# bolid-inputs-lv.net
KiCad netlist of a schematic drawn in Altium Designer
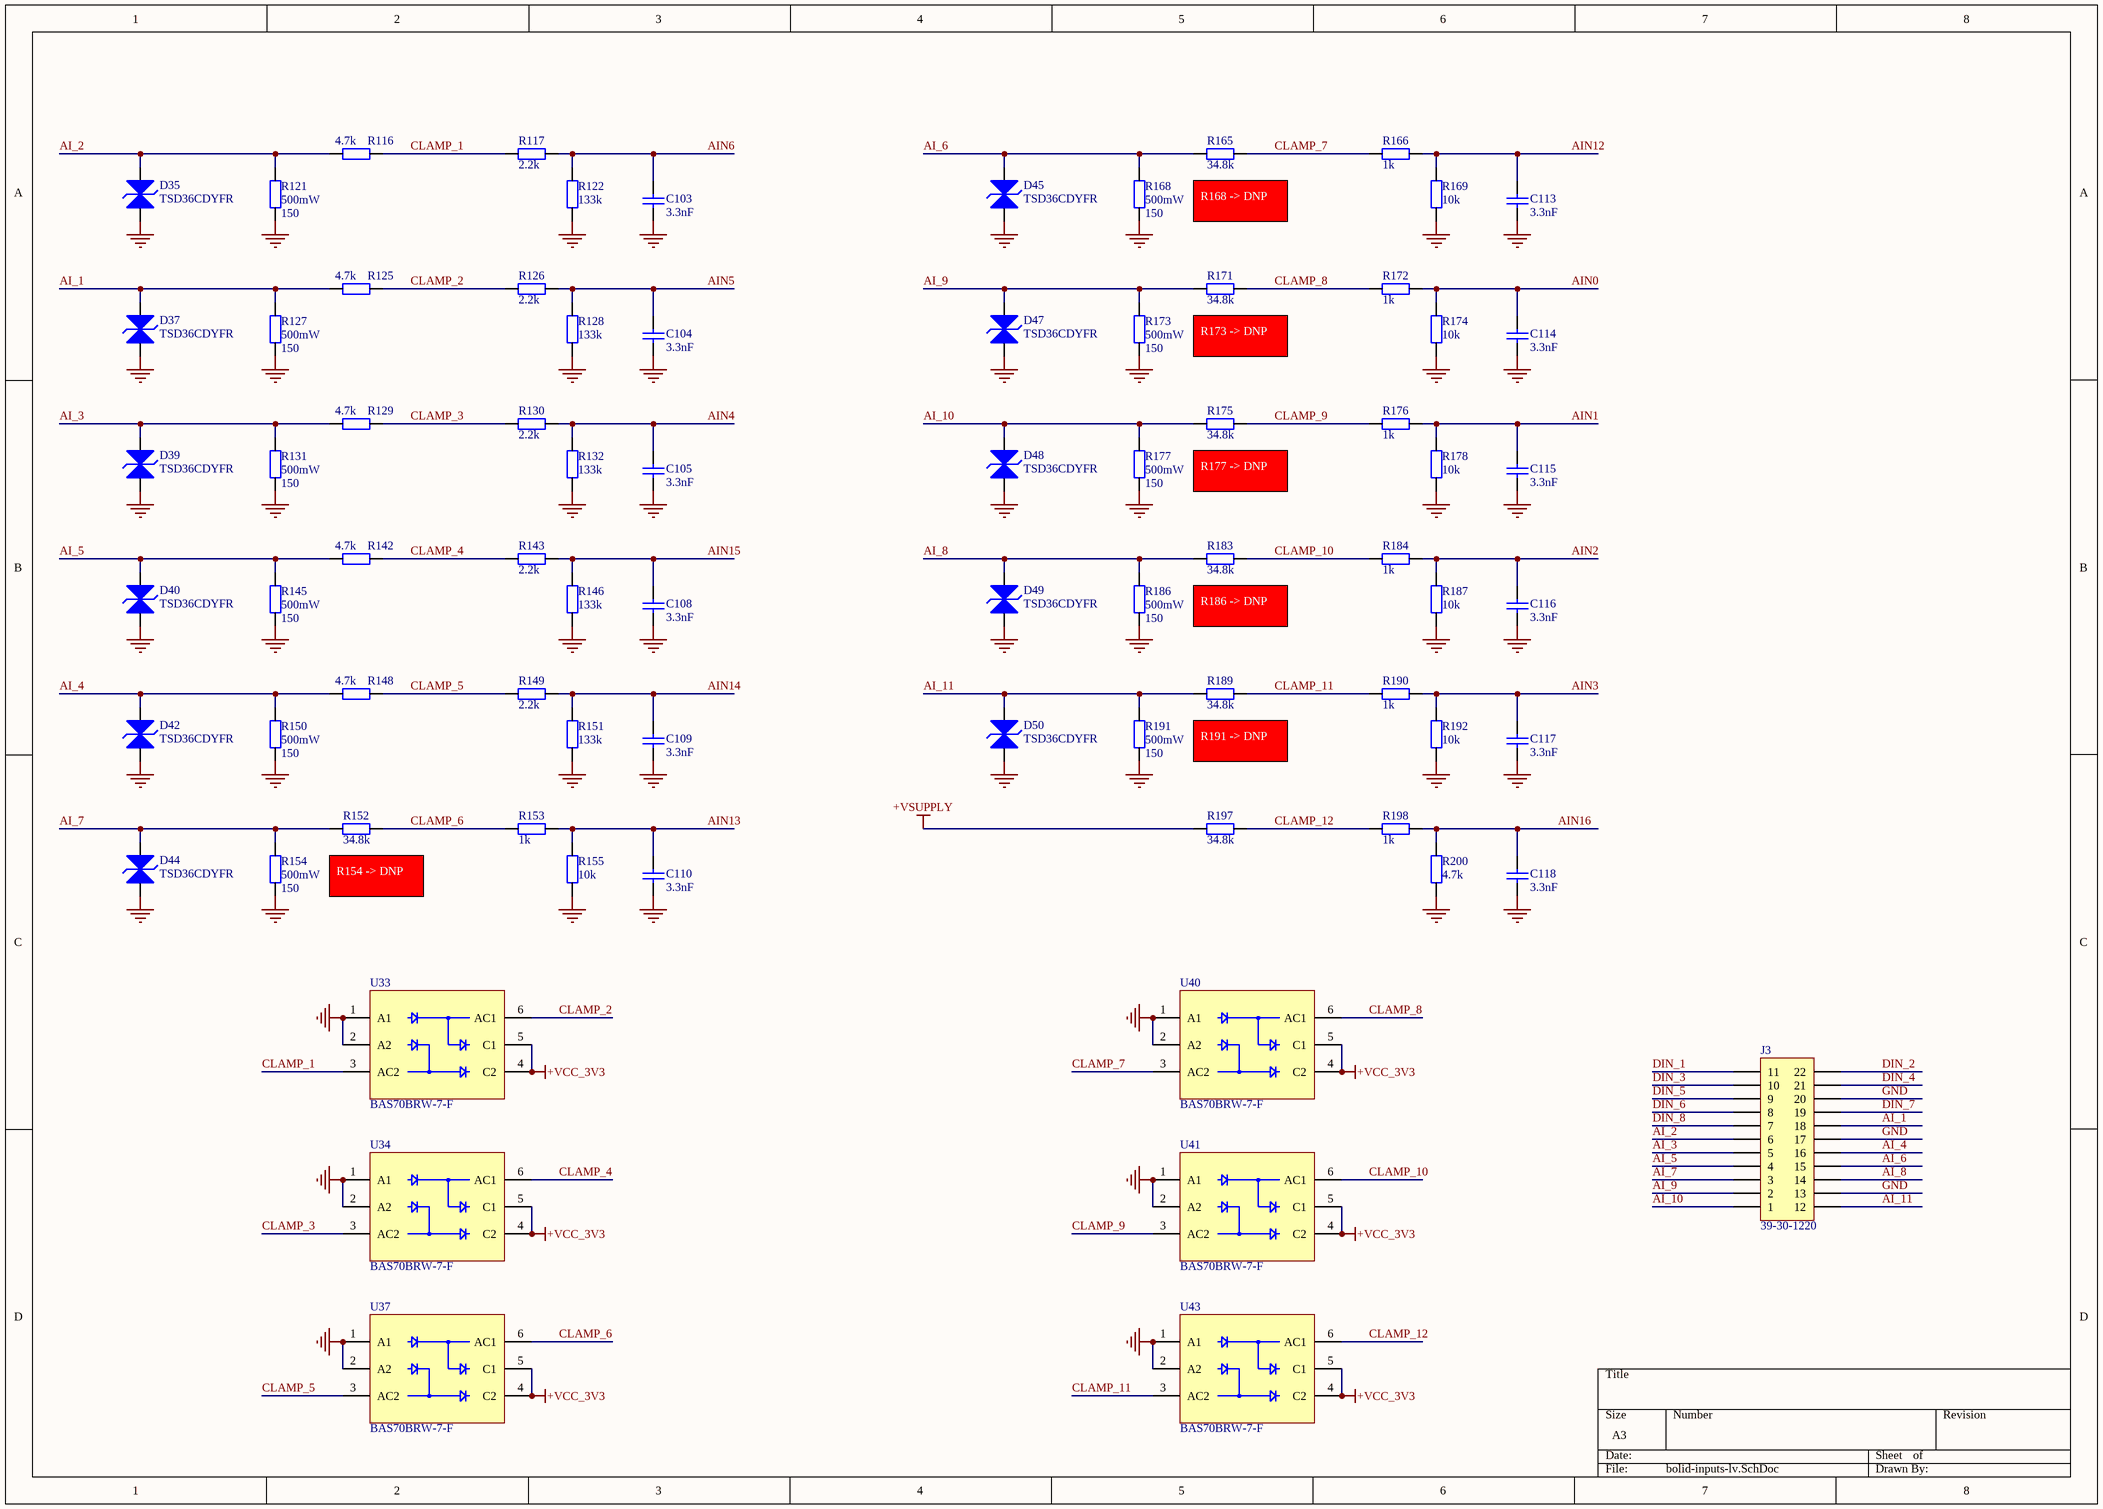
[diagram p0: bolid-inputs-lv.SchDoc]

(export (version "E")
  (design (tool "Eeschema 10.0.6"))
  (components
    (comp (ref "C103")
      (value "GRM155R71H332JA01J")
      (footprint "C0402-CAPC100X50X55L22 - Tayio Yuden TDK")
      (description "MLCC 0402 (1005) 3.3nF 5% 50V X7R")
      (fields
        (field (name "MANUFACTURER") "Murata")
        (field (name "TOLERANCE") "5%")
        (field (name "VALUE DISPLAYED") "3.3nF")
      )
      (libsource (lib "capacitors2") (part "GRM155R71H332JA01J"))
    )
    (comp (ref "C104")
      (value "GRM155R71H332JA01J")
      (footprint "C0402-CAPC100X50X55L22 - Tayio Yuden TDK")
      (description "MLCC 0402 (1005) 3.3nF 5% 50V X7R")
      (fields
        (field (name "MANUFACTURER") "Murata")
        (field (name "TOLERANCE") "5%")
        (field (name "VALUE DISPLAYED") "3.3nF")
      )
      (libsource (lib "capacitors2") (part "GRM155R71H332JA01J"))
    )
    (comp (ref "C105")
      (value "GRM155R71H332JA01J")
      (footprint "C0402-CAPC100X50X55L22 - Tayio Yuden TDK")
      (description "MLCC 0402 (1005) 3.3nF 5% 50V X7R")
      (fields
        (field (name "MANUFACTURER") "Murata")
        (field (name "TOLERANCE") "5%")
        (field (name "VALUE DISPLAYED") "3.3nF")
      )
      (libsource (lib "capacitors2") (part "GRM155R71H332JA01J"))
    )
    (comp (ref "C108")
      (value "GRM155R71H332JA01J")
      (footprint "C0402-CAPC100X50X55L22 - Tayio Yuden TDK")
      (description "MLCC 0402 (1005) 3.3nF 5% 50V X7R")
      (fields
        (field (name "MANUFACTURER") "Murata")
        (field (name "TOLERANCE") "5%")
        (field (name "VALUE DISPLAYED") "3.3nF")
      )
      (libsource (lib "capacitors2") (part "GRM155R71H332JA01J"))
    )
    (comp (ref "C109")
      (value "GRM155R71H332JA01J")
      (footprint "C0402-CAPC100X50X55L22 - Tayio Yuden TDK")
      (description "MLCC 0402 (1005) 3.3nF 5% 50V X7R")
      (fields
        (field (name "MANUFACTURER") "Murata")
        (field (name "TOLERANCE") "5%")
        (field (name "VALUE DISPLAYED") "3.3nF")
      )
      (libsource (lib "capacitors2") (part "GRM155R71H332JA01J"))
    )
    (comp (ref "C110")
      (value "GRM155R71H332JA01J")
      (footprint "C0402-CAPC100X50X55L22 - Tayio Yuden TDK")
      (description "MLCC 0402 (1005) 3.3nF 5% 50V X7R")
      (fields
        (field (name "MANUFACTURER") "Murata")
        (field (name "TOLERANCE") "5%")
        (field (name "VALUE DISPLAYED") "3.3nF")
      )
      (libsource (lib "capacitors2") (part "GRM155R71H332JA01J"))
    )
    (comp (ref "C113")
      (value "GRM155R71H332JA01J")
      (footprint "C0402-CAPC100X50X55L22 - Tayio Yuden TDK")
      (description "MLCC 0402 (1005) 3.3nF 5% 50V X7R")
      (fields
        (field (name "MANUFACTURER") "Murata")
        (field (name "TOLERANCE") "5%")
        (field (name "VALUE DISPLAYED") "3.3nF")
      )
      (libsource (lib "capacitors2") (part "GRM155R71H332JA01J"))
    )
    (comp (ref "C114")
      (value "GRM155R71H332JA01J")
      (footprint "C0402-CAPC100X50X55L22 - Tayio Yuden TDK")
      (description "MLCC 0402 (1005) 3.3nF 5% 50V X7R")
      (fields
        (field (name "MANUFACTURER") "Murata")
        (field (name "TOLERANCE") "5%")
        (field (name "VALUE DISPLAYED") "3.3nF")
      )
      (libsource (lib "capacitors2") (part "GRM155R71H332JA01J"))
    )
    (comp (ref "C115")
      (value "GRM155R71H332JA01J")
      (footprint "C0402-CAPC100X50X55L22 - Tayio Yuden TDK")
      (description "MLCC 0402 (1005) 3.3nF 5% 50V X7R")
      (fields
        (field (name "MANUFACTURER") "Murata")
        (field (name "TOLERANCE") "5%")
        (field (name "VALUE DISPLAYED") "3.3nF")
      )
      (libsource (lib "capacitors2") (part "GRM155R71H332JA01J"))
    )
    (comp (ref "C116")
      (value "GRM155R71H332JA01J")
      (footprint "C0402-CAPC100X50X55L22 - Tayio Yuden TDK")
      (description "MLCC 0402 (1005) 3.3nF 5% 50V X7R")
      (fields
        (field (name "MANUFACTURER") "Murata")
        (field (name "TOLERANCE") "5%")
        (field (name "VALUE DISPLAYED") "3.3nF")
      )
      (libsource (lib "capacitors2") (part "GRM155R71H332JA01J"))
    )
    (comp (ref "C117")
      (value "GRM155R71H332JA01J")
      (footprint "C0402-CAPC100X50X55L22 - Tayio Yuden TDK")
      (description "MLCC 0402 (1005) 3.3nF 5% 50V X7R")
      (fields
        (field (name "MANUFACTURER") "Murata")
        (field (name "TOLERANCE") "5%")
        (field (name "VALUE DISPLAYED") "3.3nF")
      )
      (libsource (lib "capacitors2") (part "GRM155R71H332JA01J"))
    )
    (comp (ref "C118")
      (value "GRM155R71H332JA01J")
      (footprint "C0402-CAPC100X50X55L22 - Tayio Yuden TDK")
      (description "MLCC 0402 (1005) 3.3nF 5% 50V X7R")
      (fields
        (field (name "MANUFACTURER") "Murata")
        (field (name "TOLERANCE") "5%")
        (field (name "VALUE DISPLAYED") "3.3nF")
      )
      (libsource (lib "capacitors2") (part "GRM155R71H332JA01J"))
    )
    (comp (ref "D35")
      (value "TSD36CDYFR")
      (footprint "SOD-323 DYF0002A TI - BIDIRECTIONAL")
      (description "36V bidirectional surge protection diode in SOD323 package 2-SOT -55 to 150")
      (fields (field (name "MANUFACTURER") "Texas Instruments"))
      (libsource (lib "semiconductors2") (part "TSD36CDYFR"))
    )
    (comp (ref "D37")
      (value "TSD36CDYFR")
      (footprint "SOD-323 DYF0002A TI - BIDIRECTIONAL")
      (description "36V bidirectional surge protection diode in SOD323 package 2-SOT -55 to 150")
      (fields (field (name "MANUFACTURER") "Texas Instruments"))
      (libsource (lib "semiconductors2") (part "TSD36CDYFR"))
    )
    (comp (ref "D39")
      (value "TSD36CDYFR")
      (footprint "SOD-323 DYF0002A TI - BIDIRECTIONAL")
      (description "36V bidirectional surge protection diode in SOD323 package 2-SOT -55 to 150")
      (fields (field (name "MANUFACTURER") "Texas Instruments"))
      (libsource (lib "semiconductors2") (part "TSD36CDYFR"))
    )
    (comp (ref "D40")
      (value "TSD36CDYFR")
      (footprint "SOD-323 DYF0002A TI - BIDIRECTIONAL")
      (description "36V bidirectional surge protection diode in SOD323 package 2-SOT -55 to 150")
      (fields (field (name "MANUFACTURER") "Texas Instruments"))
      (libsource (lib "semiconductors2") (part "TSD36CDYFR"))
    )
    (comp (ref "D42")
      (value "TSD36CDYFR")
      (footprint "SOD-323 DYF0002A TI - BIDIRECTIONAL")
      (description "36V bidirectional surge protection diode in SOD323 package 2-SOT -55 to 150")
      (fields (field (name "MANUFACTURER") "Texas Instruments"))
      (libsource (lib "semiconductors2") (part "TSD36CDYFR"))
    )
    (comp (ref "D44")
      (value "TSD36CDYFR")
      (footprint "SOD-323 DYF0002A TI - BIDIRECTIONAL")
      (description "36V bidirectional surge protection diode in SOD323 package 2-SOT -55 to 150")
      (fields (field (name "MANUFACTURER") "Texas Instruments"))
      (libsource (lib "semiconductors2") (part "TSD36CDYFR"))
    )
    (comp (ref "D45")
      (value "TSD36CDYFR")
      (footprint "SOD-323 DYF0002A TI - BIDIRECTIONAL")
      (description "36V bidirectional surge protection diode in SOD323 package 2-SOT -55 to 150")
      (fields (field (name "MANUFACTURER") "Texas Instruments"))
      (libsource (lib "semiconductors2") (part "TSD36CDYFR"))
    )
    (comp (ref "D47")
      (value "TSD36CDYFR")
      (footprint "SOD-323 DYF0002A TI - BIDIRECTIONAL")
      (description "36V bidirectional surge protection diode in SOD323 package 2-SOT -55 to 150")
      (fields (field (name "MANUFACTURER") "Texas Instruments"))
      (libsource (lib "semiconductors2") (part "TSD36CDYFR"))
    )
    (comp (ref "D48")
      (value "TSD36CDYFR")
      (footprint "SOD-323 DYF0002A TI - BIDIRECTIONAL")
      (description "36V bidirectional surge protection diode in SOD323 package 2-SOT -55 to 150")
      (fields (field (name "MANUFACTURER") "Texas Instruments"))
      (libsource (lib "semiconductors2") (part "TSD36CDYFR"))
    )
    (comp (ref "D49")
      (value "TSD36CDYFR")
      (footprint "SOD-323 DYF0002A TI - BIDIRECTIONAL")
      (description "36V bidirectional surge protection diode in SOD323 package 2-SOT -55 to 150")
      (fields (field (name "MANUFACTURER") "Texas Instruments"))
      (libsource (lib "semiconductors2") (part "TSD36CDYFR"))
    )
    (comp (ref "D50")
      (value "TSD36CDYFR")
      (footprint "SOD-323 DYF0002A TI - BIDIRECTIONAL")
      (description "36V bidirectional surge protection diode in SOD323 package 2-SOT -55 to 150")
      (fields (field (name "MANUFACTURER") "Texas Instruments"))
      (libsource (lib "semiconductors2") (part "TSD36CDYFR"))
    )
    (comp (ref "J3")
      (value "39-30-1220")
      (footprint "MOLEX Mini-Fit Jr 039301220 2x11 Peg")
      (description "Molex MiniFit Jr 2x11 Peg Conn Power HDR 22 POS 4.2mm Solder RA Thru-Hole 22 Terminal 1 Port Bag")
      (fields (field (name "MANUFACTURER") "Molex"))
      (libsource (lib "connectors2") (part "039301220"))
    )
    (comp (ref "R116")
      (value "4.7k")
      (footprint "R0402-RESC100X50X40L22N")
      (description "RES 0402 (1005) 4.70k 1% 0.063W 50V Thick Film")
      (fields
        (field (name "MANUFACTURER") "Yageo")
        (field (name "MANUFACTURER PART NUMBER") "RC0402FR-074K7L")
      )
      (libsource (lib "resistors2") (part "RC0402FR-074K7L"))
    )
    (comp (ref "R117")
      (value "2.2k")
      (footprint "R0402-RESC100X50X40L22N")
      (description "RES 0402 (1005) 2.20k 1% 0.0625W 50V Thick Film")
      (fields
        (field (name "MANUFACTURER") "Yageo")
        (field (name "MANUFACTURER PART NUMBER") "RC0402FR-072K2L")
      )
      (libsource (lib "resistors2") (part "RC0402FR-072K2L"))
    )
    (comp (ref "R121")
      (value "150")
      (footprint "R1210-RESC3126X06N - Yageo")
      (description "RES 1210 (3225) 150.0R 1% 0.500W 200V Thick Film")
      (fields
        (field (name "MANUFACTURER") "Yageo")
        (field (name "MANUFACTURER PART NUMBER") "RC1210FR-07150RL")
        (field (name "POWER RATING") "500mW")
      )
      (libsource (lib "resistors2") (part "RC1210FR-07150RL"))
    )
    (comp (ref "R122")
      (value "133k")
      (footprint "R0402-RESC100X50X40L22N")
      (description "RES 0402 (1005) 133.0k 1% 0.0625W 50V Thick Film")
      (fields
        (field (name "MANUFACTURER") "Yageo")
        (field (name "MANUFACTURER PART NUMBER") "RC0402FR-07133KL")
      )
      (libsource (lib "resistors2") (part "RC0402FR-07133KL"))
    )
    (comp (ref "R125")
      (value "4.7k")
      (footprint "R0402-RESC100X50X40L22N")
      (description "RES 0402 (1005) 4.70k 1% 0.063W 50V Thick Film")
      (fields
        (field (name "MANUFACTURER") "Yageo")
        (field (name "MANUFACTURER PART NUMBER") "RC0402FR-074K7L")
      )
      (libsource (lib "resistors2") (part "RC0402FR-074K7L"))
    )
    (comp (ref "R126")
      (value "2.2k")
      (footprint "R0402-RESC100X50X40L22N")
      (description "RES 0402 (1005) 2.20k 1% 0.0625W 50V Thick Film")
      (fields
        (field (name "MANUFACTURER") "Yageo")
        (field (name "MANUFACTURER PART NUMBER") "RC0402FR-072K2L")
      )
      (libsource (lib "resistors2") (part "RC0402FR-072K2L"))
    )
    (comp (ref "R127")
      (value "150")
      (footprint "R1210-RESC3126X06N - Yageo")
      (description "RES 1210 (3225) 150.0R 1% 0.500W 200V Thick Film")
      (fields
        (field (name "MANUFACTURER") "Yageo")
        (field (name "MANUFACTURER PART NUMBER") "RC1210FR-07150RL")
        (field (name "POWER RATING") "500mW")
      )
      (libsource (lib "resistors2") (part "RC1210FR-07150RL"))
    )
    (comp (ref "R128")
      (value "133k")
      (footprint "R0402-RESC100X50X40L22N")
      (description "RES 0402 (1005) 133.0k 1% 0.0625W 50V Thick Film")
      (fields
        (field (name "MANUFACTURER") "Yageo")
        (field (name "MANUFACTURER PART NUMBER") "RC0402FR-07133KL")
      )
      (libsource (lib "resistors2") (part "RC0402FR-07133KL"))
    )
    (comp (ref "R129")
      (value "4.7k")
      (footprint "R0402-RESC100X50X40L22N")
      (description "RES 0402 (1005) 4.70k 1% 0.063W 50V Thick Film")
      (fields
        (field (name "MANUFACTURER") "Yageo")
        (field (name "MANUFACTURER PART NUMBER") "RC0402FR-074K7L")
      )
      (libsource (lib "resistors2") (part "RC0402FR-074K7L"))
    )
    (comp (ref "R130")
      (value "2.2k")
      (footprint "R0402-RESC100X50X40L22N")
      (description "RES 0402 (1005) 2.20k 1% 0.0625W 50V Thick Film")
      (fields
        (field (name "MANUFACTURER") "Yageo")
        (field (name "MANUFACTURER PART NUMBER") "RC0402FR-072K2L")
      )
      (libsource (lib "resistors2") (part "RC0402FR-072K2L"))
    )
    (comp (ref "R131")
      (value "150")
      (footprint "R1210-RESC3126X06N - Yageo")
      (description "RES 1210 (3225) 150.0R 1% 0.500W 200V Thick Film")
      (fields
        (field (name "MANUFACTURER") "Yageo")
        (field (name "MANUFACTURER PART NUMBER") "RC1210FR-07150RL")
        (field (name "POWER RATING") "500mW")
      )
      (libsource (lib "resistors2") (part "RC1210FR-07150RL"))
    )
    (comp (ref "R132")
      (value "133k")
      (footprint "R0402-RESC100X50X40L22N")
      (description "RES 0402 (1005) 133.0k 1% 0.0625W 50V Thick Film")
      (fields
        (field (name "MANUFACTURER") "Yageo")
        (field (name "MANUFACTURER PART NUMBER") "RC0402FR-07133KL")
      )
      (libsource (lib "resistors2") (part "RC0402FR-07133KL"))
    )
    (comp (ref "R142")
      (value "4.7k")
      (footprint "R0402-RESC100X50X40L22N")
      (description "RES 0402 (1005) 4.70k 1% 0.063W 50V Thick Film")
      (fields
        (field (name "MANUFACTURER") "Yageo")
        (field (name "MANUFACTURER PART NUMBER") "RC0402FR-074K7L")
      )
      (libsource (lib "resistors2") (part "RC0402FR-074K7L"))
    )
    (comp (ref "R143")
      (value "2.2k")
      (footprint "R0402-RESC100X50X40L22N")
      (description "RES 0402 (1005) 2.20k 1% 0.0625W 50V Thick Film")
      (fields
        (field (name "MANUFACTURER") "Yageo")
        (field (name "MANUFACTURER PART NUMBER") "RC0402FR-072K2L")
      )
      (libsource (lib "resistors2") (part "RC0402FR-072K2L"))
    )
    (comp (ref "R145")
      (value "150")
      (footprint "R1210-RESC3126X06N - Yageo")
      (description "RES 1210 (3225) 150.0R 1% 0.500W 200V Thick Film")
      (fields
        (field (name "MANUFACTURER") "Yageo")
        (field (name "MANUFACTURER PART NUMBER") "RC1210FR-07150RL")
        (field (name "POWER RATING") "500mW")
      )
      (libsource (lib "resistors2") (part "RC1210FR-07150RL"))
    )
    (comp (ref "R146")
      (value "133k")
      (footprint "R0402-RESC100X50X40L22N")
      (description "RES 0402 (1005) 133.0k 1% 0.0625W 50V Thick Film")
      (fields
        (field (name "MANUFACTURER") "Yageo")
        (field (name "MANUFACTURER PART NUMBER") "RC0402FR-07133KL")
      )
      (libsource (lib "resistors2") (part "RC0402FR-07133KL"))
    )
    (comp (ref "R148")
      (value "4.7k")
      (footprint "R0402-RESC100X50X40L22N")
      (description "RES 0402 (1005) 4.70k 1% 0.063W 50V Thick Film")
      (fields
        (field (name "MANUFACTURER") "Yageo")
        (field (name "MANUFACTURER PART NUMBER") "RC0402FR-074K7L")
      )
      (libsource (lib "resistors2") (part "RC0402FR-074K7L"))
    )
    (comp (ref "R149")
      (value "2.2k")
      (footprint "R0402-RESC100X50X40L22N")
      (description "RES 0402 (1005) 2.20k 1% 0.0625W 50V Thick Film")
      (fields
        (field (name "MANUFACTURER") "Yageo")
        (field (name "MANUFACTURER PART NUMBER") "RC0402FR-072K2L")
      )
      (libsource (lib "resistors2") (part "RC0402FR-072K2L"))
    )
    (comp (ref "R150")
      (value "150")
      (footprint "R1210-RESC3126X06N - Yageo")
      (description "RES 1210 (3225) 150.0R 1% 0.500W 200V Thick Film")
      (fields
        (field (name "MANUFACTURER") "Yageo")
        (field (name "MANUFACTURER PART NUMBER") "RC1210FR-07150RL")
        (field (name "POWER RATING") "500mW")
      )
      (libsource (lib "resistors2") (part "RC1210FR-07150RL"))
    )
    (comp (ref "R151")
      (value "133k")
      (footprint "R0402-RESC100X50X40L22N")
      (description "RES 0402 (1005) 133.0k 1% 0.0625W 50V Thick Film")
      (fields
        (field (name "MANUFACTURER") "Yageo")
        (field (name "MANUFACTURER PART NUMBER") "RC0402FR-07133KL")
      )
      (libsource (lib "resistors2") (part "RC0402FR-07133KL"))
    )
    (comp (ref "R152")
      (value "34.8k")
      (footprint "R0402-RESC100X50X40L22N")
      (description "RES 0402 (1005) 34.8k 1% 0.0625W 50V Thick Film")
      (fields
        (field (name "MANUFACTURER") "Yageo")
        (field (name "MANUFACTURER PART NUMBER") "RC0402FR-0734K8L")
      )
      (libsource (lib "resistors2") (part "RC0402FR-0734K8L"))
    )
    (comp (ref "R153")
      (value "1k")
      (footprint "R0402-RESC100X50X40L22N")
      (description "RES 0402 (1005) 1.00k 1% 0.0625W 50V Thick Film")
      (fields
        (field (name "MANUFACTURER") "Yageo")
        (field (name "MANUFACTURER PART NUMBER") "RC0402FR-071KL")
      )
      (libsource (lib "resistors2") (part "RC0402FR-071KL"))
    )
    (comp (ref "R154")
      (value "150")
      (footprint "R1210-RESC3126X06N - Yageo")
      (description "RES 1210 (3225) 150.0R 1% 0.500W 200V Thick Film")
      (fields
        (field (name "MANUFACTURER") "Yageo")
        (field (name "MANUFACTURER PART NUMBER") "RC1210FR-07150RL")
        (field (name "POWER RATING") "500mW")
      )
      (libsource (lib "resistors2") (part "RC1210FR-07150RL"))
    )
    (comp (ref "R155")
      (value "10k")
      (footprint "R0402-RESC100X50X40L22N")
      (description "RES 0402 (1005) 10.0k 1% 0.0625W 50V Thick Film")
      (fields
        (field (name "MANUFACTURER") "Yageo")
        (field (name "MANUFACTURER PART NUMBER") "RC0402FR-0710KL")
      )
      (libsource (lib "resistors2") (part "RC0402FR-0710KL"))
    )
    (comp (ref "R165")
      (value "34.8k")
      (footprint "R0402-RESC100X50X40L22N")
      (description "RES 0402 (1005) 34.8k 1% 0.0625W 50V Thick Film")
      (fields
        (field (name "MANUFACTURER") "Yageo")
        (field (name "MANUFACTURER PART NUMBER") "RC0402FR-0734K8L")
      )
      (libsource (lib "resistors2") (part "RC0402FR-0734K8L"))
    )
    (comp (ref "R166")
      (value "1k")
      (footprint "R0402-RESC100X50X40L22N")
      (description "RES 0402 (1005) 1.00k 1% 0.0625W 50V Thick Film")
      (fields
        (field (name "MANUFACTURER") "Yageo")
        (field (name "MANUFACTURER PART NUMBER") "RC0402FR-071KL")
      )
      (libsource (lib "resistors2") (part "RC0402FR-071KL"))
    )
    (comp (ref "R168")
      (value "150")
      (footprint "R1210-RESC3126X06N - Yageo")
      (description "RES 1210 (3225) 150.0R 1% 0.500W 200V Thick Film")
      (fields
        (field (name "MANUFACTURER") "Yageo")
        (field (name "MANUFACTURER PART NUMBER") "RC1210FR-07150RL")
        (field (name "POWER RATING") "500mW")
      )
      (libsource (lib "resistors2") (part "RC1210FR-07150RL"))
    )
    (comp (ref "R169")
      (value "10k")
      (footprint "R0402-RESC100X50X40L22N")
      (description "RES 0402 (1005) 10.0k 1% 0.0625W 50V Thick Film")
      (fields
        (field (name "MANUFACTURER") "Yageo")
        (field (name "MANUFACTURER PART NUMBER") "RC0402FR-0710KL")
      )
      (libsource (lib "resistors2") (part "RC0402FR-0710KL"))
    )
    (comp (ref "R171")
      (value "34.8k")
      (footprint "R0402-RESC100X50X40L22N")
      (description "RES 0402 (1005) 34.8k 1% 0.0625W 50V Thick Film")
      (fields
        (field (name "MANUFACTURER") "Yageo")
        (field (name "MANUFACTURER PART NUMBER") "RC0402FR-0734K8L")
      )
      (libsource (lib "resistors2") (part "RC0402FR-0734K8L"))
    )
    (comp (ref "R172")
      (value "1k")
      (footprint "R0402-RESC100X50X40L22N")
      (description "RES 0402 (1005) 1.00k 1% 0.0625W 50V Thick Film")
      (fields
        (field (name "MANUFACTURER") "Yageo")
        (field (name "MANUFACTURER PART NUMBER") "RC0402FR-071KL")
      )
      (libsource (lib "resistors2") (part "RC0402FR-071KL"))
    )
    (comp (ref "R173")
      (value "150")
      (footprint "R1210-RESC3126X06N - Yageo")
      (description "RES 1210 (3225) 150.0R 1% 0.500W 200V Thick Film")
      (fields
        (field (name "MANUFACTURER") "Yageo")
        (field (name "MANUFACTURER PART NUMBER") "RC1210FR-07150RL")
        (field (name "POWER RATING") "500mW")
      )
      (libsource (lib "resistors2") (part "RC1210FR-07150RL"))
    )
    (comp (ref "R174")
      (value "10k")
      (footprint "R0402-RESC100X50X40L22N")
      (description "RES 0402 (1005) 10.0k 1% 0.0625W 50V Thick Film")
      (fields
        (field (name "MANUFACTURER") "Yageo")
        (field (name "MANUFACTURER PART NUMBER") "RC0402FR-0710KL")
      )
      (libsource (lib "resistors2") (part "RC0402FR-0710KL"))
    )
    (comp (ref "R175")
      (value "34.8k")
      (footprint "R0402-RESC100X50X40L22N")
      (description "RES 0402 (1005) 34.8k 1% 0.0625W 50V Thick Film")
      (fields
        (field (name "MANUFACTURER") "Yageo")
        (field (name "MANUFACTURER PART NUMBER") "RC0402FR-0734K8L")
      )
      (libsource (lib "resistors2") (part "RC0402FR-0734K8L"))
    )
    (comp (ref "R176")
      (value "1k")
      (footprint "R0402-RESC100X50X40L22N")
      (description "RES 0402 (1005) 1.00k 1% 0.0625W 50V Thick Film")
      (fields
        (field (name "MANUFACTURER") "Yageo")
        (field (name "MANUFACTURER PART NUMBER") "RC0402FR-071KL")
      )
      (libsource (lib "resistors2") (part "RC0402FR-071KL"))
    )
    (comp (ref "R177")
      (value "150")
      (footprint "R1210-RESC3126X06N - Yageo")
      (description "RES 1210 (3225) 150.0R 1% 0.500W 200V Thick Film")
      (fields
        (field (name "MANUFACTURER") "Yageo")
        (field (name "MANUFACTURER PART NUMBER") "RC1210FR-07150RL")
        (field (name "POWER RATING") "500mW")
      )
      (libsource (lib "resistors2") (part "RC1210FR-07150RL"))
    )
    (comp (ref "R178")
      (value "10k")
      (footprint "R0402-RESC100X50X40L22N")
      (description "RES 0402 (1005) 10.0k 1% 0.0625W 50V Thick Film")
      (fields
        (field (name "MANUFACTURER") "Yageo")
        (field (name "MANUFACTURER PART NUMBER") "RC0402FR-0710KL")
      )
      (libsource (lib "resistors2") (part "RC0402FR-0710KL"))
    )
    (comp (ref "R183")
      (value "34.8k")
      (footprint "R0402-RESC100X50X40L22N")
      (description "RES 0402 (1005) 34.8k 1% 0.0625W 50V Thick Film")
      (fields
        (field (name "MANUFACTURER") "Yageo")
        (field (name "MANUFACTURER PART NUMBER") "RC0402FR-0734K8L")
      )
      (libsource (lib "resistors2") (part "RC0402FR-0734K8L"))
    )
    (comp (ref "R184")
      (value "1k")
      (footprint "R0402-RESC100X50X40L22N")
      (description "RES 0402 (1005) 1.00k 1% 0.0625W 50V Thick Film")
      (fields
        (field (name "MANUFACTURER") "Yageo")
        (field (name "MANUFACTURER PART NUMBER") "RC0402FR-071KL")
      )
      (libsource (lib "resistors2") (part "RC0402FR-071KL"))
    )
    (comp (ref "R186")
      (value "150")
      (footprint "R1210-RESC3126X06N - Yageo")
      (description "RES 1210 (3225) 150.0R 1% 0.500W 200V Thick Film")
      (fields
        (field (name "MANUFACTURER") "Yageo")
        (field (name "MANUFACTURER PART NUMBER") "RC1210FR-07150RL")
        (field (name "POWER RATING") "500mW")
      )
      (libsource (lib "resistors2") (part "RC1210FR-07150RL"))
    )
    (comp (ref "R187")
      (value "10k")
      (footprint "R0402-RESC100X50X40L22N")
      (description "RES 0402 (1005) 10.0k 1% 0.0625W 50V Thick Film")
      (fields
        (field (name "MANUFACTURER") "Yageo")
        (field (name "MANUFACTURER PART NUMBER") "RC0402FR-0710KL")
      )
      (libsource (lib "resistors2") (part "RC0402FR-0710KL"))
    )
    (comp (ref "R189")
      (value "34.8k")
      (footprint "R0402-RESC100X50X40L22N")
      (description "RES 0402 (1005) 34.8k 1% 0.0625W 50V Thick Film")
      (fields
        (field (name "MANUFACTURER") "Yageo")
        (field (name "MANUFACTURER PART NUMBER") "RC0402FR-0734K8L")
      )
      (libsource (lib "resistors2") (part "RC0402FR-0734K8L"))
    )
    (comp (ref "R190")
      (value "1k")
      (footprint "R0402-RESC100X50X40L22N")
      (description "RES 0402 (1005) 1.00k 1% 0.0625W 50V Thick Film")
      (fields
        (field (name "MANUFACTURER") "Yageo")
        (field (name "MANUFACTURER PART NUMBER") "RC0402FR-071KL")
      )
      (libsource (lib "resistors2") (part "RC0402FR-071KL"))
    )
    (comp (ref "R191")
      (value "150")
      (footprint "R1210-RESC3126X06N - Yageo")
      (description "RES 1210 (3225) 150.0R 1% 0.500W 200V Thick Film")
      (fields
        (field (name "MANUFACTURER") "Yageo")
        (field (name "MANUFACTURER PART NUMBER") "RC1210FR-07150RL")
        (field (name "POWER RATING") "500mW")
      )
      (libsource (lib "resistors2") (part "RC1210FR-07150RL"))
    )
    (comp (ref "R192")
      (value "10k")
      (footprint "R0402-RESC100X50X40L22N")
      (description "RES 0402 (1005) 10.0k 1% 0.0625W 50V Thick Film")
      (fields
        (field (name "MANUFACTURER") "Yageo")
        (field (name "MANUFACTURER PART NUMBER") "RC0402FR-0710KL")
      )
      (libsource (lib "resistors2") (part "RC0402FR-0710KL"))
    )
    (comp (ref "R197")
      (value "34.8k")
      (footprint "R0402-RESC100X50X40L22N")
      (description "RES 0402 (1005) 34.8k 1% 0.0625W 50V Thick Film")
      (fields
        (field (name "MANUFACTURER") "Yageo")
        (field (name "MANUFACTURER PART NUMBER") "RC0402FR-0734K8L")
      )
      (libsource (lib "resistors2") (part "RC0402FR-0734K8L"))
    )
    (comp (ref "R198")
      (value "1k")
      (footprint "R0402-RESC100X50X40L22N")
      (description "RES 0402 (1005) 1.00k 1% 0.0625W 50V Thick Film")
      (fields
        (field (name "MANUFACTURER") "Yageo")
        (field (name "MANUFACTURER PART NUMBER") "RC0402FR-071KL")
      )
      (libsource (lib "resistors2") (part "RC0402FR-071KL"))
    )
    (comp (ref "R200")
      (value "4.7k")
      (footprint "R0402-RESC100X50X40L22N")
      (description "RES 0402 (1005) 4.70k 1% 0.063W 50V Thick Film")
      (fields
        (field (name "MANUFACTURER") "Yageo")
        (field (name "MANUFACTURER PART NUMBER") "RC0402FR-074K7L")
      )
      (libsource (lib "") (part "RC0402FR-074K7L_1"))
    )
    (comp (ref "U33")
      (value "BAS70BRW-7-F")
      (footprint "SOT363 DIODES DS30158 Rev. 14-2 SOT65P210X110-6N")
      (description "BAS70BRW Series 70 V 100 mA Surface Mount Schottky Barrier Diode Arrays SOT-363")
      (fields (field (name "MANUFACTURER") "Diodes"))
      (libsource (lib "semiconductors2") (part "BAS70BRW-7-F"))
    )
    (comp (ref "U34")
      (value "BAS70BRW-7-F")
      (footprint "SOT363 DIODES DS30158 Rev. 14-2 SOT65P210X110-6N")
      (description "BAS70BRW Series 70 V 100 mA Surface Mount Schottky Barrier Diode Arrays SOT-363")
      (fields (field (name "MANUFACTURER") "Diodes"))
      (libsource (lib "semiconductors2") (part "BAS70BRW-7-F"))
    )
    (comp (ref "U37")
      (value "BAS70BRW-7-F")
      (footprint "SOT363 DIODES DS30158 Rev. 14-2 SOT65P210X110-6N")
      (description "BAS70BRW Series 70 V 100 mA Surface Mount Schottky Barrier Diode Arrays SOT-363")
      (fields (field (name "MANUFACTURER") "Diodes"))
      (libsource (lib "semiconductors2") (part "BAS70BRW-7-F"))
    )
    (comp (ref "U40")
      (value "BAS70BRW-7-F")
      (footprint "SOT363 DIODES DS30158 Rev. 14-2 SOT65P210X110-6N")
      (description "BAS70BRW Series 70 V 100 mA Surface Mount Schottky Barrier Diode Arrays SOT-363")
      (fields (field (name "MANUFACTURER") "Diodes"))
      (libsource (lib "semiconductors2") (part "BAS70BRW-7-F"))
    )
    (comp (ref "U41")
      (value "BAS70BRW-7-F")
      (footprint "SOT363 DIODES DS30158 Rev. 14-2 SOT65P210X110-6N")
      (description "BAS70BRW Series 70 V 100 mA Surface Mount Schottky Barrier Diode Arrays SOT-363")
      (fields (field (name "MANUFACTURER") "Diodes"))
      (libsource (lib "semiconductors2") (part "BAS70BRW-7-F"))
    )
    (comp (ref "U43")
      (value "BAS70BRW-7-F")
      (footprint "SOT363 DIODES DS30158 Rev. 14-2 SOT65P210X110-6N")
      (description "BAS70BRW Series 70 V 100 mA Surface Mount Schottky Barrier Diode Arrays SOT-363")
      (fields (field (name "MANUFACTURER") "Diodes"))
      (libsource (lib "semiconductors2") (part "BAS70BRW-7-F"))
    )
  )
  (nets
    (net (code "1") (name "+VCC_3V3") (class "Default")
      (node (ref "U33") (pin "4") (pinfunction "C2_4") (pintype "passive"))
      (node (ref "U33") (pin "5") (pinfunction "C1_5") (pintype "passive"))
      (node (ref "U34") (pin "4") (pinfunction "C2_4") (pintype "passive"))
      (node (ref "U34") (pin "5") (pinfunction "C1_5") (pintype "passive"))
      (node (ref "U37") (pin "4") (pinfunction "C2_4") (pintype "passive"))
      (node (ref "U37") (pin "5") (pinfunction "C1_5") (pintype "passive"))
      (node (ref "U40") (pin "4") (pinfunction "C2_4") (pintype "passive"))
      (node (ref "U40") (pin "5") (pinfunction "C1_5") (pintype "passive"))
      (node (ref "U41") (pin "4") (pinfunction "C2_4") (pintype "passive"))
      (node (ref "U41") (pin "5") (pinfunction "C1_5") (pintype "passive"))
      (node (ref "U43") (pin "4") (pinfunction "C2_4") (pintype "passive"))
      (node (ref "U43") (pin "5") (pinfunction "C1_5") (pintype "passive"))
    )
    (net (code "2") (name "+VSUPPLY") (class "Default")
      (node (ref "R197") (pin "1") (pinfunction "1_1") (pintype "passive"))
    )
    (net (code "3") (name "/AIN0") (class "Default")
      (node (ref "C114") (pin "2") (pinfunction "2_2") (pintype "passive"))
      (node (ref "R172") (pin "2") (pinfunction "2_2") (pintype "passive"))
      (node (ref "R174") (pin "2") (pinfunction "2_2") (pintype "passive"))
    )
    (net (code "4") (name "/AIN1") (class "Default")
      (node (ref "C115") (pin "2") (pinfunction "2_2") (pintype "passive"))
      (node (ref "R176") (pin "2") (pinfunction "2_2") (pintype "passive"))
      (node (ref "R178") (pin "2") (pinfunction "2_2") (pintype "passive"))
    )
    (net (code "5") (name "/AIN2") (class "Default")
      (node (ref "C116") (pin "2") (pinfunction "2_2") (pintype "passive"))
      (node (ref "R184") (pin "2") (pinfunction "2_2") (pintype "passive"))
      (node (ref "R187") (pin "2") (pinfunction "2_2") (pintype "passive"))
    )
    (net (code "6") (name "/AIN3") (class "Default")
      (node (ref "C117") (pin "2") (pinfunction "2_2") (pintype "passive"))
      (node (ref "R190") (pin "2") (pinfunction "2_2") (pintype "passive"))
      (node (ref "R192") (pin "2") (pinfunction "2_2") (pintype "passive"))
    )
    (net (code "7") (name "/AIN4") (class "Default")
      (node (ref "C105") (pin "2") (pinfunction "2_2") (pintype "passive"))
      (node (ref "R130") (pin "1") (pinfunction "1_1") (pintype "passive"))
      (node (ref "R132") (pin "2") (pinfunction "2_2") (pintype "passive"))
    )
    (net (code "8") (name "/AIN5") (class "Default")
      (node (ref "C104") (pin "2") (pinfunction "2_2") (pintype "passive"))
      (node (ref "R126") (pin "1") (pinfunction "1_1") (pintype "passive"))
      (node (ref "R128") (pin "2") (pinfunction "2_2") (pintype "passive"))
    )
    (net (code "9") (name "/AIN6") (class "Default")
      (node (ref "C103") (pin "2") (pinfunction "2_2") (pintype "passive"))
      (node (ref "R117") (pin "1") (pinfunction "1_1") (pintype "passive"))
      (node (ref "R122") (pin "2") (pinfunction "2_2") (pintype "passive"))
    )
    (net (code "10") (name "/AIN12") (class "Default")
      (node (ref "C113") (pin "2") (pinfunction "2_2") (pintype "passive"))
      (node (ref "R166") (pin "2") (pinfunction "2_2") (pintype "passive"))
      (node (ref "R169") (pin "2") (pinfunction "2_2") (pintype "passive"))
    )
    (net (code "11") (name "/AIN13") (class "Default")
      (node (ref "C110") (pin "2") (pinfunction "2_2") (pintype "passive"))
      (node (ref "R153") (pin "2") (pinfunction "2_2") (pintype "passive"))
      (node (ref "R155") (pin "2") (pinfunction "2_2") (pintype "passive"))
    )
    (net (code "12") (name "/AIN14") (class "Default")
      (node (ref "C109") (pin "2") (pinfunction "2_2") (pintype "passive"))
      (node (ref "R149") (pin "1") (pinfunction "1_1") (pintype "passive"))
      (node (ref "R151") (pin "2") (pinfunction "2_2") (pintype "passive"))
    )
    (net (code "13") (name "/AIN15") (class "Default")
      (node (ref "C108") (pin "2") (pinfunction "2_2") (pintype "passive"))
      (node (ref "R143") (pin "1") (pinfunction "1_1") (pintype "passive"))
      (node (ref "R146") (pin "2") (pinfunction "2_2") (pintype "passive"))
    )
    (net (code "14") (name "/AIN16") (class "Default")
      (node (ref "C118") (pin "2") (pinfunction "2_2") (pintype "passive"))
      (node (ref "R198") (pin "2") (pinfunction "2_2") (pintype "passive"))
      (node (ref "R200") (pin "2") (pinfunction "2_2") (pintype "passive"))
    )
    (net (code "15") (name "/AI_1") (class "Default")
      (node (ref "D37") (pin "2") (pinfunction "2_2") (pintype "passive"))
      (node (ref "J3") (pin "18") (pinfunction "18_18") (pintype "passive"))
      (node (ref "R125") (pin "1") (pinfunction "1_1") (pintype "passive"))
      (node (ref "R127") (pin "2") (pinfunction "2_2") (pintype "passive"))
    )
    (net (code "16") (name "/AI_2") (class "Default")
      (node (ref "D35") (pin "2") (pinfunction "2_2") (pintype "passive"))
      (node (ref "J3") (pin "6") (pinfunction "6_6") (pintype "passive"))
      (node (ref "R116") (pin "1") (pinfunction "1_1") (pintype "passive"))
      (node (ref "R121") (pin "2") (pinfunction "2_2") (pintype "passive"))
    )
    (net (code "17") (name "/AI_3") (class "Default")
      (node (ref "D39") (pin "2") (pinfunction "2_2") (pintype "passive"))
      (node (ref "J3") (pin "5") (pinfunction "5_5") (pintype "passive"))
      (node (ref "R129") (pin "1") (pinfunction "1_1") (pintype "passive"))
      (node (ref "R131") (pin "2") (pinfunction "2_2") (pintype "passive"))
    )
    (net (code "18") (name "/AI_4") (class "Default")
      (node (ref "D42") (pin "2") (pinfunction "2_2") (pintype "passive"))
      (node (ref "J3") (pin "16") (pinfunction "16_16") (pintype "passive"))
      (node (ref "R148") (pin "1") (pinfunction "1_1") (pintype "passive"))
      (node (ref "R150") (pin "2") (pinfunction "2_2") (pintype "passive"))
    )
    (net (code "19") (name "/AI_5") (class "Default")
      (node (ref "D40") (pin "2") (pinfunction "2_2") (pintype "passive"))
      (node (ref "J3") (pin "4") (pinfunction "4_4") (pintype "passive"))
      (node (ref "R142") (pin "1") (pinfunction "1_1") (pintype "passive"))
      (node (ref "R145") (pin "2") (pinfunction "2_2") (pintype "passive"))
    )
    (net (code "20") (name "/AI_6") (class "Default")
      (node (ref "D45") (pin "2") (pinfunction "2_2") (pintype "passive"))
      (node (ref "J3") (pin "15") (pinfunction "15_15") (pintype "passive"))
      (node (ref "R165") (pin "1") (pinfunction "1_1") (pintype "passive"))
      (node (ref "R168") (pin "2") (pinfunction "2_2") (pintype "passive"))
    )
    (net (code "21") (name "/AI_7") (class "Default")
      (node (ref "D44") (pin "2") (pinfunction "2_2") (pintype "passive"))
      (node (ref "J3") (pin "3") (pinfunction "3_3") (pintype "passive"))
      (node (ref "R152") (pin "1") (pinfunction "1_1") (pintype "passive"))
      (node (ref "R154") (pin "2") (pinfunction "2_2") (pintype "passive"))
    )
    (net (code "22") (name "/AI_8") (class "Default")
      (node (ref "D49") (pin "2") (pinfunction "2_2") (pintype "passive"))
      (node (ref "J3") (pin "14") (pinfunction "14_14") (pintype "passive"))
      (node (ref "R183") (pin "1") (pinfunction "1_1") (pintype "passive"))
      (node (ref "R186") (pin "2") (pinfunction "2_2") (pintype "passive"))
    )
    (net (code "23") (name "/AI_9") (class "Default")
      (node (ref "D47") (pin "2") (pinfunction "2_2") (pintype "passive"))
      (node (ref "J3") (pin "2") (pinfunction "2_2") (pintype "passive"))
      (node (ref "R171") (pin "1") (pinfunction "1_1") (pintype "passive"))
      (node (ref "R173") (pin "2") (pinfunction "2_2") (pintype "passive"))
    )
    (net (code "24") (name "/AI_10") (class "Default")
      (node (ref "D48") (pin "2") (pinfunction "2_2") (pintype "passive"))
      (node (ref "J3") (pin "1") (pinfunction "1_1") (pintype "passive"))
      (node (ref "R175") (pin "1") (pinfunction "1_1") (pintype "passive"))
      (node (ref "R177") (pin "2") (pinfunction "2_2") (pintype "passive"))
    )
    (net (code "25") (name "/AI_11") (class "Default")
      (node (ref "D50") (pin "2") (pinfunction "2_2") (pintype "passive"))
      (node (ref "J3") (pin "12") (pinfunction "12_12") (pintype "passive"))
      (node (ref "R189") (pin "1") (pinfunction "1_1") (pintype "passive"))
      (node (ref "R191") (pin "2") (pinfunction "2_2") (pintype "passive"))
    )
    (net (code "26") (name "/CLAMP_1") (class "Default")
      (node (ref "R116") (pin "2") (pinfunction "2_2") (pintype "passive"))
      (node (ref "R117") (pin "2") (pinfunction "2_2") (pintype "passive"))
      (node (ref "U33") (pin "3") (pinfunction "AC2_3") (pintype "passive"))
    )
    (net (code "27") (name "/CLAMP_2") (class "Default")
      (node (ref "R125") (pin "2") (pinfunction "2_2") (pintype "passive"))
      (node (ref "R126") (pin "2") (pinfunction "2_2") (pintype "passive"))
      (node (ref "U33") (pin "6") (pinfunction "AC1_6") (pintype "passive"))
    )
    (net (code "28") (name "/CLAMP_3") (class "Default")
      (node (ref "R129") (pin "2") (pinfunction "2_2") (pintype "passive"))
      (node (ref "R130") (pin "2") (pinfunction "2_2") (pintype "passive"))
      (node (ref "U34") (pin "3") (pinfunction "AC2_3") (pintype "passive"))
    )
    (net (code "29") (name "/CLAMP_4") (class "Default")
      (node (ref "R142") (pin "2") (pinfunction "2_2") (pintype "passive"))
      (node (ref "R143") (pin "2") (pinfunction "2_2") (pintype "passive"))
      (node (ref "U34") (pin "6") (pinfunction "AC1_6") (pintype "passive"))
    )
    (net (code "30") (name "/CLAMP_5") (class "Default")
      (node (ref "R148") (pin "2") (pinfunction "2_2") (pintype "passive"))
      (node (ref "R149") (pin "2") (pinfunction "2_2") (pintype "passive"))
      (node (ref "U37") (pin "3") (pinfunction "AC2_3") (pintype "passive"))
    )
    (net (code "31") (name "/CLAMP_6") (class "Default")
      (node (ref "R152") (pin "2") (pinfunction "2_2") (pintype "passive"))
      (node (ref "R153") (pin "1") (pinfunction "1_1") (pintype "passive"))
      (node (ref "U37") (pin "6") (pinfunction "AC1_6") (pintype "passive"))
    )
    (net (code "32") (name "/CLAMP_7") (class "Default")
      (node (ref "R165") (pin "2") (pinfunction "2_2") (pintype "passive"))
      (node (ref "R166") (pin "1") (pinfunction "1_1") (pintype "passive"))
      (node (ref "U40") (pin "3") (pinfunction "AC2_3") (pintype "passive"))
    )
    (net (code "33") (name "/CLAMP_8") (class "Default")
      (node (ref "R171") (pin "2") (pinfunction "2_2") (pintype "passive"))
      (node (ref "R172") (pin "1") (pinfunction "1_1") (pintype "passive"))
      (node (ref "U40") (pin "6") (pinfunction "AC1_6") (pintype "passive"))
    )
    (net (code "34") (name "/CLAMP_9") (class "Default")
      (node (ref "R175") (pin "2") (pinfunction "2_2") (pintype "passive"))
      (node (ref "R176") (pin "1") (pinfunction "1_1") (pintype "passive"))
      (node (ref "U41") (pin "3") (pinfunction "AC2_3") (pintype "passive"))
    )
    (net (code "35") (name "/CLAMP_10") (class "Default")
      (node (ref "R183") (pin "2") (pinfunction "2_2") (pintype "passive"))
      (node (ref "R184") (pin "1") (pinfunction "1_1") (pintype "passive"))
      (node (ref "U41") (pin "6") (pinfunction "AC1_6") (pintype "passive"))
    )
    (net (code "36") (name "/CLAMP_11") (class "Default")
      (node (ref "R189") (pin "2") (pinfunction "2_2") (pintype "passive"))
      (node (ref "R190") (pin "1") (pinfunction "1_1") (pintype "passive"))
      (node (ref "U43") (pin "3") (pinfunction "AC2_3") (pintype "passive"))
    )
    (net (code "37") (name "/CLAMP_12") (class "Default")
      (node (ref "R197") (pin "2") (pinfunction "2_2") (pintype "passive"))
      (node (ref "R198") (pin "1") (pinfunction "1_1") (pintype "passive"))
      (node (ref "U43") (pin "6") (pinfunction "AC1_6") (pintype "passive"))
    )
    (net (code "38") (name "/DIN_1") (class "Default")
      (node (ref "J3") (pin "11") (pinfunction "11_11") (pintype "passive"))
    )
    (net (code "39") (name "/DIN_2") (class "Default")
      (node (ref "J3") (pin "22") (pinfunction "22_22") (pintype "passive"))
    )
    (net (code "40") (name "/DIN_3") (class "Default")
      (node (ref "J3") (pin "10") (pinfunction "10_10") (pintype "passive"))
    )
    (net (code "41") (name "/DIN_4") (class "Default")
      (node (ref "J3") (pin "21") (pinfunction "21_21") (pintype "passive"))
    )
    (net (code "42") (name "/DIN_5") (class "Default")
      (node (ref "J3") (pin "9") (pinfunction "9_9") (pintype "passive"))
    )
    (net (code "43") (name "/DIN_6") (class "Default")
      (node (ref "J3") (pin "8") (pinfunction "8_8") (pintype "passive"))
    )
    (net (code "44") (name "/DIN_7") (class "Default")
      (node (ref "J3") (pin "19") (pinfunction "19_19") (pintype "passive"))
    )
    (net (code "45") (name "/DIN_8") (class "Default")
      (node (ref "J3") (pin "7") (pinfunction "7_7") (pintype "passive"))
    )
    (net (code "46") (name "GND") (class "Default")
      (node (ref "C103") (pin "1") (pinfunction "1_1") (pintype "passive"))
      (node (ref "C104") (pin "1") (pinfunction "1_1") (pintype "passive"))
      (node (ref "C105") (pin "1") (pinfunction "1_1") (pintype "passive"))
      (node (ref "C108") (pin "1") (pinfunction "1_1") (pintype "passive"))
      (node (ref "C109") (pin "1") (pinfunction "1_1") (pintype "passive"))
      (node (ref "C110") (pin "1") (pinfunction "1_1") (pintype "passive"))
      (node (ref "C113") (pin "1") (pinfunction "1_1") (pintype "passive"))
      (node (ref "C114") (pin "1") (pinfunction "1_1") (pintype "passive"))
      (node (ref "C115") (pin "1") (pinfunction "1_1") (pintype "passive"))
      (node (ref "C116") (pin "1") (pinfunction "1_1") (pintype "passive"))
      (node (ref "C117") (pin "1") (pinfunction "1_1") (pintype "passive"))
      (node (ref "C118") (pin "1") (pinfunction "1_1") (pintype "passive"))
      (node (ref "D35") (pin "1") (pinfunction "1_1") (pintype "passive"))
      (node (ref "D37") (pin "1") (pinfunction "1_1") (pintype "passive"))
      (node (ref "D39") (pin "1") (pinfunction "1_1") (pintype "passive"))
      (node (ref "D40") (pin "1") (pinfunction "1_1") (pintype "passive"))
      (node (ref "D42") (pin "1") (pinfunction "1_1") (pintype "passive"))
      (node (ref "D44") (pin "1") (pinfunction "1_1") (pintype "passive"))
      (node (ref "D45") (pin "1") (pinfunction "1_1") (pintype "passive"))
      (node (ref "D47") (pin "1") (pinfunction "1_1") (pintype "passive"))
      (node (ref "D48") (pin "1") (pinfunction "1_1") (pintype "passive"))
      (node (ref "D49") (pin "1") (pinfunction "1_1") (pintype "passive"))
      (node (ref "D50") (pin "1") (pinfunction "1_1") (pintype "passive"))
      (node (ref "J3") (pin "13") (pinfunction "13_13") (pintype "passive"))
      (node (ref "J3") (pin "17") (pinfunction "17_17") (pintype "passive"))
      (node (ref "J3") (pin "20") (pinfunction "20_20") (pintype "passive"))
      (node (ref "R121") (pin "1") (pinfunction "1_1") (pintype "passive"))
      (node (ref "R122") (pin "1") (pinfunction "1_1") (pintype "passive"))
      (node (ref "R127") (pin "1") (pinfunction "1_1") (pintype "passive"))
      (node (ref "R128") (pin "1") (pinfunction "1_1") (pintype "passive"))
      (node (ref "R131") (pin "1") (pinfunction "1_1") (pintype "passive"))
      (node (ref "R132") (pin "1") (pinfunction "1_1") (pintype "passive"))
      (node (ref "R145") (pin "1") (pinfunction "1_1") (pintype "passive"))
      (node (ref "R146") (pin "1") (pinfunction "1_1") (pintype "passive"))
      (node (ref "R150") (pin "1") (pinfunction "1_1") (pintype "passive"))
      (node (ref "R151") (pin "1") (pinfunction "1_1") (pintype "passive"))
      (node (ref "R154") (pin "1") (pinfunction "1_1") (pintype "passive"))
      (node (ref "R155") (pin "1") (pinfunction "1_1") (pintype "passive"))
      (node (ref "R168") (pin "1") (pinfunction "1_1") (pintype "passive"))
      (node (ref "R169") (pin "1") (pinfunction "1_1") (pintype "passive"))
      (node (ref "R173") (pin "1") (pinfunction "1_1") (pintype "passive"))
      (node (ref "R174") (pin "1") (pinfunction "1_1") (pintype "passive"))
      (node (ref "R177") (pin "1") (pinfunction "1_1") (pintype "passive"))
      (node (ref "R178") (pin "1") (pinfunction "1_1") (pintype "passive"))
      (node (ref "R186") (pin "1") (pinfunction "1_1") (pintype "passive"))
      (node (ref "R187") (pin "1") (pinfunction "1_1") (pintype "passive"))
      (node (ref "R191") (pin "1") (pinfunction "1_1") (pintype "passive"))
      (node (ref "R192") (pin "1") (pinfunction "1_1") (pintype "passive"))
      (node (ref "R200") (pin "1") (pinfunction "1_1") (pintype "passive"))
      (node (ref "U33") (pin "1") (pinfunction "A1_1") (pintype "passive"))
      (node (ref "U33") (pin "2") (pinfunction "A2_2") (pintype "passive"))
      (node (ref "U34") (pin "1") (pinfunction "A1_1") (pintype "passive"))
      (node (ref "U34") (pin "2") (pinfunction "A2_2") (pintype "passive"))
      (node (ref "U37") (pin "1") (pinfunction "A1_1") (pintype "passive"))
      (node (ref "U37") (pin "2") (pinfunction "A2_2") (pintype "passive"))
      (node (ref "U40") (pin "1") (pinfunction "A1_1") (pintype "passive"))
      (node (ref "U40") (pin "2") (pinfunction "A2_2") (pintype "passive"))
      (node (ref "U41") (pin "1") (pinfunction "A1_1") (pintype "passive"))
      (node (ref "U41") (pin "2") (pinfunction "A2_2") (pintype "passive"))
      (node (ref "U43") (pin "1") (pinfunction "A1_1") (pintype "passive"))
      (node (ref "U43") (pin "2") (pinfunction "A2_2") (pintype "passive"))
    )
  )
)
